# Fortin33.net
KiCad netlist of a schematic drawn in EAGLE
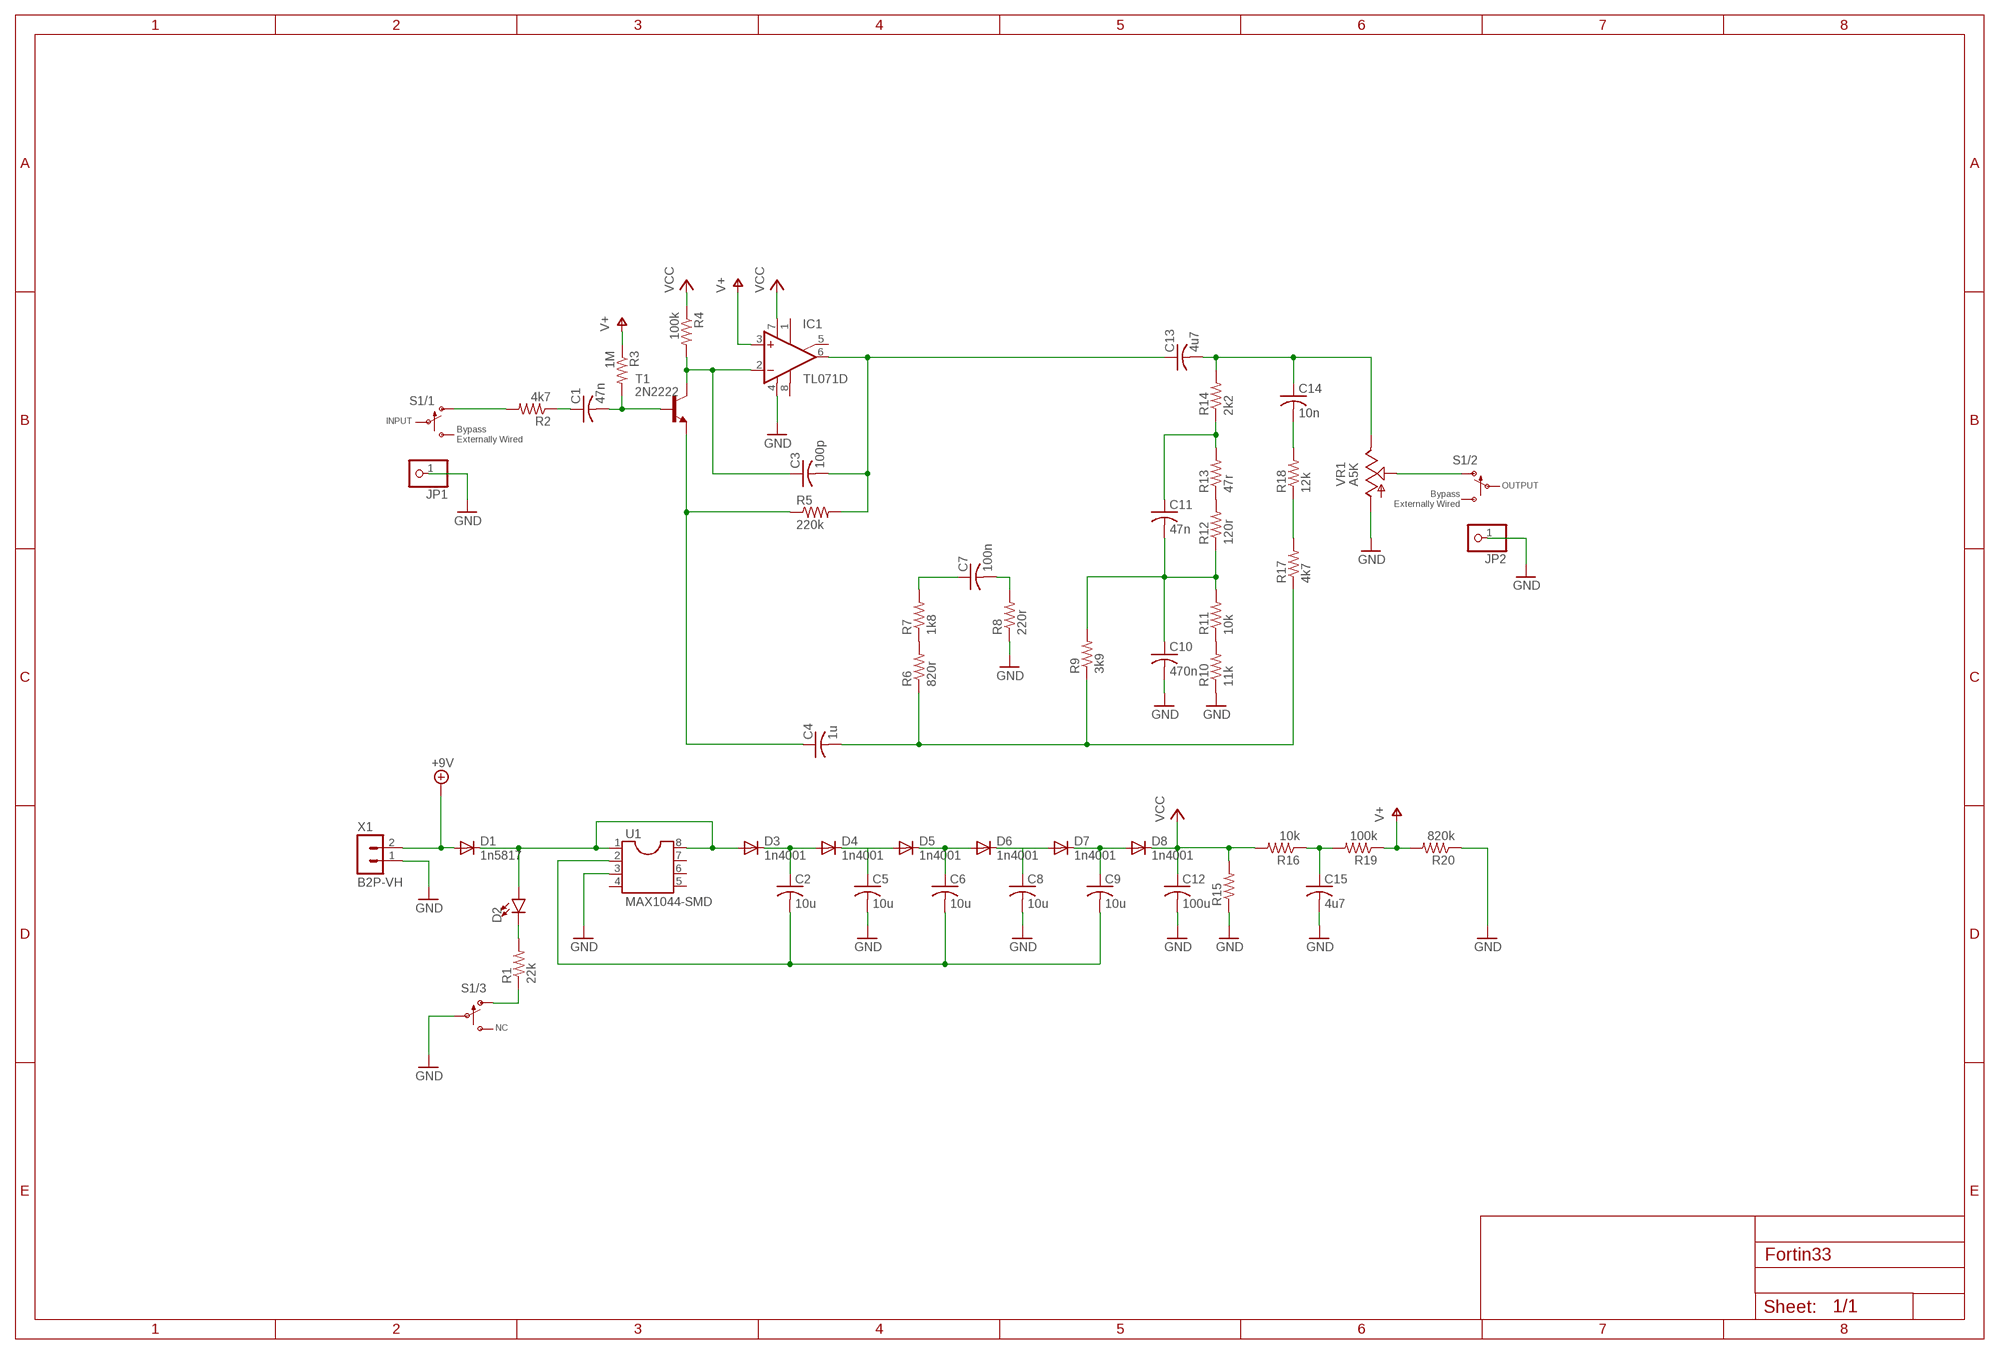
[diagram p0: schematic, sheet 1]

(export (version "E")
  (design (tool "Eeschema 10.0.6"))
  (components
    (comp (ref "C1")
      (value "47n")
      (footprint "eagle-import:C0603")
      (libsource (lib "eagle-import") (part "C-USC0603"))
    )
    (comp (ref "C2")
      (value "10u")
      (footprint "eagle-import:C050-025X075")
      (libsource (lib "eagle-import") (part "C-US050-025X075"))
    )
    (comp (ref "C3")
      (value "100p")
      (footprint "eagle-import:C0603")
      (libsource (lib "eagle-import") (part "C-USC0603"))
    )
    (comp (ref "C4")
      (value "1u")
      (footprint "eagle-import:C0603")
      (libsource (lib "eagle-import") (part "C-USC0603"))
    )
    (comp (ref "C5")
      (value "10u")
      (footprint "eagle-import:C050-025X075")
      (libsource (lib "eagle-import") (part "C-US050-025X075"))
    )
    (comp (ref "C6")
      (value "10u")
      (footprint "eagle-import:C050-025X075")
      (libsource (lib "eagle-import") (part "C-US050-025X075"))
    )
    (comp (ref "C7")
      (value "100n")
      (footprint "eagle-import:C0603")
      (libsource (lib "eagle-import") (part "C-USC0603"))
    )
    (comp (ref "C8")
      (value "10u")
      (footprint "eagle-import:C050-025X075")
      (libsource (lib "eagle-import") (part "C-US050-025X075"))
    )
    (comp (ref "C9")
      (value "10u")
      (footprint "eagle-import:C050-025X075")
      (libsource (lib "eagle-import") (part "C-US050-025X075"))
    )
    (comp (ref "C10")
      (value "470n")
      (footprint "eagle-import:C0603")
      (libsource (lib "eagle-import") (part "C-USC0603"))
    )
    (comp (ref "C11")
      (value "47n")
      (footprint "eagle-import:C0603")
      (libsource (lib "eagle-import") (part "C-USC0603"))
    )
    (comp (ref "C12")
      (value "100u")
      (footprint "eagle-import:C075-063X106")
      (libsource (lib "eagle-import") (part "C-US075-063X106"))
    )
    (comp (ref "C13")
      (value "4u7")
      (footprint "eagle-import:C0603")
      (libsource (lib "eagle-import") (part "C-USC0603"))
    )
    (comp (ref "C14")
      (value "10n")
      (footprint "eagle-import:C0603")
      (libsource (lib "eagle-import") (part "C-USC0603"))
    )
    (comp (ref "C15")
      (value "4u7")
      (footprint "eagle-import:C050-025X075")
      (libsource (lib "eagle-import") (part "C-US050-025X075"))
    )
    (comp (ref "D1")
      (value "1n5817")
      (footprint "eagle-import:DO41-10")
      (libsource (lib "eagle-import") (part "1N4004"))
    )
    (comp (ref "D2")
      (value "LED3MM")
      (footprint "eagle-import:LED_3MM")
      (libsource (lib "eagle-import") (part "LED3MM"))
    )
    (comp (ref "D3")
      (value "1n4001")
      (footprint "eagle-import:DO41-10")
      (libsource (lib "eagle-import") (part "1N4004"))
    )
    (comp (ref "D4")
      (value "1n4001")
      (footprint "eagle-import:DO41-10")
      (libsource (lib "eagle-import") (part "1N4004"))
    )
    (comp (ref "D5")
      (value "1n4001")
      (footprint "eagle-import:DO41-10")
      (libsource (lib "eagle-import") (part "1N4004"))
    )
    (comp (ref "D6")
      (value "1n4001")
      (footprint "eagle-import:DO41-10")
      (libsource (lib "eagle-import") (part "1N4004"))
    )
    (comp (ref "D7")
      (value "1n4001")
      (footprint "eagle-import:DO41-10")
      (libsource (lib "eagle-import") (part "1N4004"))
    )
    (comp (ref "D8")
      (value "1n4001")
      (footprint "eagle-import:DO41-10")
      (libsource (lib "eagle-import") (part "1N4004"))
    )
    (comp (ref "IC1")
      (value "TL071D")
      (footprint "eagle-import:SO08")
      (libsource (lib "eagle-import") (part "TL071D"))
    )
    (comp (ref "JP1")
      (value "PINHD-1X1")
      (footprint "eagle-import:1X01")
      (libsource (lib "eagle-import") (part "PINHD-1X1"))
    )
    (comp (ref "JP2")
      (value "PINHD-1X1")
      (footprint "eagle-import:1X01")
      (libsource (lib "eagle-import") (part "PINHD-1X1"))
    )
    (comp (ref "R1")
      (value "22k")
      (footprint "eagle-import:R0603")
      (libsource (lib "eagle-import") (part "R-US_R0603"))
    )
    (comp (ref "R2")
      (value "4k7")
      (footprint "eagle-import:R0603")
      (libsource (lib "eagle-import") (part "R-US_R0603"))
    )
    (comp (ref "R3")
      (value "1M")
      (footprint "eagle-import:R0603")
      (libsource (lib "eagle-import") (part "R-US_R0603"))
    )
    (comp (ref "R4")
      (value "100k")
      (footprint "eagle-import:R0603")
      (libsource (lib "eagle-import") (part "R-US_R0603"))
    )
    (comp (ref "R5")
      (value "220k")
      (footprint "eagle-import:R0603")
      (libsource (lib "eagle-import") (part "R-US_R0603"))
    )
    (comp (ref "R6")
      (value "820r")
      (footprint "eagle-import:R0603")
      (libsource (lib "eagle-import") (part "R-US_R0603"))
    )
    (comp (ref "R7")
      (value "1k8")
      (footprint "eagle-import:R0603")
      (libsource (lib "eagle-import") (part "R-US_R0603"))
    )
    (comp (ref "R8")
      (value "220r")
      (footprint "eagle-import:R0603")
      (libsource (lib "eagle-import") (part "R-US_R0603"))
    )
    (comp (ref "R9")
      (value "3k9")
      (footprint "eagle-import:R0603")
      (libsource (lib "eagle-import") (part "R-US_R0603"))
    )
    (comp (ref "R10")
      (value "11k")
      (footprint "eagle-import:R0603")
      (libsource (lib "eagle-import") (part "R-US_R0603"))
    )
    (comp (ref "R11")
      (value "10k")
      (footprint "eagle-import:R0603")
      (libsource (lib "eagle-import") (part "R-US_R0603"))
    )
    (comp (ref "R12")
      (value "120r")
      (footprint "eagle-import:R0603")
      (libsource (lib "eagle-import") (part "R-US_R0603"))
    )
    (comp (ref "R13")
      (value "47r")
      (footprint "eagle-import:R0603")
      (libsource (lib "eagle-import") (part "R-US_R0603"))
    )
    (comp (ref "R14")
      (value "2k2")
      (footprint "eagle-import:R0603")
      (libsource (lib "eagle-import") (part "R-US_R0603"))
    )
    (comp (ref "R15")
      (value "R-US_R0603")
      (footprint "eagle-import:R0603")
      (libsource (lib "eagle-import") (part "R-US_R0603"))
    )
    (comp (ref "R16")
      (value "10k")
      (footprint "eagle-import:R0603")
      (libsource (lib "eagle-import") (part "R-US_R0603"))
    )
    (comp (ref "R17")
      (value "4k7")
      (footprint "eagle-import:R0603")
      (libsource (lib "eagle-import") (part "R-US_R0603"))
    )
    (comp (ref "R18")
      (value "12k")
      (footprint "eagle-import:R0603")
      (libsource (lib "eagle-import") (part "R-US_R0603"))
    )
    (comp (ref "R19")
      (value "100k")
      (footprint "eagle-import:R0603")
      (libsource (lib "eagle-import") (part "R-US_R0603"))
    )
    (comp (ref "R20")
      (value "820k")
      (footprint "eagle-import:R0603")
      (libsource (lib "eagle-import") (part "R-US_R0603"))
    )
    (comp (ref "S1")
      (value "SWITCH-3DPT-INLINE-BREAKOUT-BYPASS")
      (footprint "eagle-import:1X04")
      (libsource (lib "eagle-import") (part "SWITCH-3DPT-INLINE-BREAKOUT-BYPASS"))
    )
    (comp (ref "T1")
      (value "2N2222")
      (footprint "eagle-import:TO92-EBC-OVAL")
      (libsource (lib "eagle-import") (part "2N2222"))
    )
    (comp (ref "U1")
      (value "MAX1044-SMD")
      (footprint "eagle-import:SO-08")
      (libsource (lib "eagle-import") (part "MAX1044-SMD"))
    )
    (comp (ref "VR1")
      (value "A5K")
      (footprint "eagle-import:ALPHA-16-MINI")
      (libsource (lib "eagle-import") (part "16MM-POT"))
    )
    (comp (ref "X1")
      (value "B2P-VH")
      (footprint "eagle-import:B2P-VH")
      (libsource (lib "eagle-import") (part "B2P-VH"))
    )
  )
  (nets
    (net (code "1") (name "+9V") (class "Default")
      (node (ref "D1") (pin "A") (pinfunction "A_A") (pintype "passive"))
      (node (ref "X1") (pin "2") (pinfunction "2_2") (pintype "passive"))
    )
    (net (code "2") (name "GND") (class "Default")
      (node (ref "C10") (pin "2") (pinfunction "2_2") (pintype "passive"))
      (node (ref "C12") (pin "2") (pinfunction "2_2") (pintype "passive"))
      (node (ref "C15") (pin "2") (pinfunction "2_2") (pintype "passive"))
      (node (ref "C5") (pin "2") (pinfunction "2_2") (pintype "passive"))
      (node (ref "C8") (pin "2") (pinfunction "2_2") (pintype "passive"))
      (node (ref "IC1") (pin "4") (pinfunction "V-_4") (pintype "power_in"))
      (node (ref "JP1") (pin "1") (pinfunction "1_1") (pintype "passive"))
      (node (ref "JP2") (pin "1") (pinfunction "1_1") (pintype "passive"))
      (node (ref "R10") (pin "1") (pinfunction "1_1") (pintype "passive"))
      (node (ref "R15") (pin "1") (pinfunction "1_1") (pintype "passive"))
      (node (ref "R20") (pin "1") (pinfunction "1_1") (pintype "passive"))
      (node (ref "R8") (pin "1") (pinfunction "1_1") (pintype "passive"))
      (node (ref "S1") (pin "3") (pinfunction "COMMON_3") (pintype "passive"))
      (node (ref "U1") (pin "3") (pinfunction "3_3") (pintype "passive"))
      (node (ref "VR1") (pin "LEFT") (pinfunction "LEFT_LEFT") (pintype "passive"))
      (node (ref "X1") (pin "1") (pinfunction "1_1") (pintype "passive"))
    )
    (net (code "3") (name "Net-(C1-Pad1)") (class "Default")
      (node (ref "C1") (pin "1") (pinfunction "1_1") (pintype "passive"))
      (node (ref "R2") (pin "1") (pinfunction "1_1") (pintype "passive"))
    )
    (net (code "4") (name "Net-(C1-Pad2)") (class "Default")
      (node (ref "C1") (pin "2") (pinfunction "2_2") (pintype "passive"))
      (node (ref "R3") (pin "2") (pinfunction "2_2") (pintype "passive"))
      (node (ref "T1") (pin "B") (pinfunction "B_B") (pintype "passive"))
    )
    (net (code "5") (name "Net-(C2-Pad1)") (class "Default")
      (node (ref "C2") (pin "1") (pinfunction "1_1") (pintype "passive"))
      (node (ref "D3") (pin "C") (pinfunction "C_C") (pintype "passive"))
      (node (ref "D4") (pin "A") (pinfunction "A_A") (pintype "passive"))
    )
    (net (code "6") (name "Net-(C2-Pad2)") (class "Default")
      (node (ref "C2") (pin "2") (pinfunction "2_2") (pintype "passive"))
      (node (ref "C6") (pin "2") (pinfunction "2_2") (pintype "passive"))
      (node (ref "C9") (pin "2") (pinfunction "2_2") (pintype "passive"))
      (node (ref "U1") (pin "2") (pinfunction "2_2") (pintype "passive"))
    )
    (net (code "7") (name "Net-(C4-Pad1)") (class "Default")
      (node (ref "C4") (pin "1") (pinfunction "1_1") (pintype "passive"))
      (node (ref "R5") (pin "1") (pinfunction "1_1") (pintype "passive"))
      (node (ref "T1") (pin "E") (pinfunction "E_E") (pintype "passive"))
    )
    (net (code "8") (name "Net-(C4-Pad2)") (class "Default")
      (node (ref "C4") (pin "2") (pinfunction "2_2") (pintype "passive"))
      (node (ref "R17") (pin "1") (pinfunction "1_1") (pintype "passive"))
      (node (ref "R6") (pin "1") (pinfunction "1_1") (pintype "passive"))
      (node (ref "R9") (pin "1") (pinfunction "1_1") (pintype "passive"))
    )
    (net (code "9") (name "Net-(C5-Pad1)") (class "Default")
      (node (ref "C5") (pin "1") (pinfunction "1_1") (pintype "passive"))
      (node (ref "D4") (pin "C") (pinfunction "C_C") (pintype "passive"))
      (node (ref "D5") (pin "A") (pinfunction "A_A") (pintype "passive"))
    )
    (net (code "10") (name "Net-(C6-Pad1)") (class "Default")
      (node (ref "C6") (pin "1") (pinfunction "1_1") (pintype "passive"))
      (node (ref "D5") (pin "C") (pinfunction "C_C") (pintype "passive"))
      (node (ref "D6") (pin "A") (pinfunction "A_A") (pintype "passive"))
    )
    (net (code "11") (name "Net-(C7-Pad1)") (class "Default")
      (node (ref "C7") (pin "1") (pinfunction "1_1") (pintype "passive"))
      (node (ref "R7") (pin "2") (pinfunction "2_2") (pintype "passive"))
    )
    (net (code "12") (name "Net-(C7-Pad2)") (class "Default")
      (node (ref "C7") (pin "2") (pinfunction "2_2") (pintype "passive"))
      (node (ref "R8") (pin "2") (pinfunction "2_2") (pintype "passive"))
    )
    (net (code "13") (name "Net-(C8-Pad1)") (class "Default")
      (node (ref "C8") (pin "1") (pinfunction "1_1") (pintype "passive"))
      (node (ref "D6") (pin "C") (pinfunction "C_C") (pintype "passive"))
      (node (ref "D7") (pin "A") (pinfunction "A_A") (pintype "passive"))
    )
    (net (code "14") (name "Net-(C9-Pad1)") (class "Default")
      (node (ref "C9") (pin "1") (pinfunction "1_1") (pintype "passive"))
      (node (ref "D7") (pin "C") (pinfunction "C_C") (pintype "passive"))
      (node (ref "D8") (pin "A") (pinfunction "A_A") (pintype "passive"))
    )
    (net (code "15") (name "Net-(C10-Pad1)") (class "Default")
      (node (ref "C10") (pin "1") (pinfunction "1_1") (pintype "passive"))
      (node (ref "C11") (pin "2") (pinfunction "2_2") (pintype "passive"))
      (node (ref "R11") (pin "2") (pinfunction "2_2") (pintype "passive"))
      (node (ref "R12") (pin "1") (pinfunction "1_1") (pintype "passive"))
      (node (ref "R9") (pin "2") (pinfunction "2_2") (pintype "passive"))
    )
    (net (code "16") (name "Net-(C11-Pad1)") (class "Default")
      (node (ref "C11") (pin "1") (pinfunction "1_1") (pintype "passive"))
      (node (ref "R13") (pin "2") (pinfunction "2_2") (pintype "passive"))
      (node (ref "R14") (pin "1") (pinfunction "1_1") (pintype "passive"))
    )
    (net (code "17") (name "Net-(C13-Pad2)") (class "Default")
      (node (ref "C13") (pin "2") (pinfunction "2_2") (pintype "passive"))
      (node (ref "C14") (pin "1") (pinfunction "1_1") (pintype "passive"))
      (node (ref "R14") (pin "2") (pinfunction "2_2") (pintype "passive"))
      (node (ref "VR1") (pin "RIGHT") (pinfunction "RIGHT_RIGHT") (pintype "passive"))
    )
    (net (code "18") (name "Net-(C14-Pad2)") (class "Default")
      (node (ref "C14") (pin "2") (pinfunction "2_2") (pintype "passive"))
      (node (ref "R18") (pin "2") (pinfunction "2_2") (pintype "passive"))
    )
    (net (code "19") (name "Net-(C15-Pad1)") (class "Default")
      (node (ref "C15") (pin "1") (pinfunction "1_1") (pintype "passive"))
      (node (ref "R16") (pin "1") (pinfunction "1_1") (pintype "passive"))
      (node (ref "R19") (pin "2") (pinfunction "2_2") (pintype "passive"))
    )
    (net (code "20") (name "Net-(D1-PadC)") (class "Default")
      (node (ref "D1") (pin "C") (pinfunction "C_C") (pintype "passive"))
      (node (ref "D2") (pin "A") (pinfunction "A_A") (pintype "passive"))
      (node (ref "D3") (pin "A") (pinfunction "A_A") (pintype "passive"))
      (node (ref "U1") (pin "1") (pinfunction "1_1") (pintype "passive"))
      (node (ref "U1") (pin "8") (pinfunction "8_8") (pintype "passive"))
    )
    (net (code "21") (name "Net-(D2-C)") (class "Default")
      (node (ref "D2") (pin "K") (pinfunction "C_K") (pintype "passive"))
      (node (ref "R1") (pin "2") (pinfunction "2_2") (pintype "passive"))
    )
    (net (code "22") (name "Net-(IC1--IN)") (class "Default")
      (node (ref "C3") (pin "1") (pinfunction "1_1") (pintype "passive"))
      (node (ref "IC1") (pin "2") (pinfunction "-IN_2") (pintype "input"))
      (node (ref "R4") (pin "2") (pinfunction "2_2") (pintype "passive"))
      (node (ref "T1") (pin "C") (pinfunction "C_C") (pintype "passive"))
    )
    (net (code "23") (name "Net-(IC1-OUT)") (class "Default")
      (node (ref "C13") (pin "1") (pinfunction "1_1") (pintype "passive"))
      (node (ref "C3") (pin "2") (pinfunction "2_2") (pintype "passive"))
      (node (ref "IC1") (pin "6") (pinfunction "OUT_6") (pintype "output"))
      (node (ref "R5") (pin "2") (pinfunction "2_2") (pintype "passive"))
    )
    (net (code "24") (name "Net-(R6-Pad2)") (class "Default")
      (node (ref "R6") (pin "2") (pinfunction "2_2") (pintype "passive"))
      (node (ref "R7") (pin "1") (pinfunction "1_1") (pintype "passive"))
    )
    (net (code "25") (name "Net-(R10-Pad2)") (class "Default")
      (node (ref "R10") (pin "2") (pinfunction "2_2") (pintype "passive"))
      (node (ref "R11") (pin "1") (pinfunction "1_1") (pintype "passive"))
    )
    (net (code "26") (name "Net-(R12-Pad2)") (class "Default")
      (node (ref "R12") (pin "2") (pinfunction "2_2") (pintype "passive"))
      (node (ref "R13") (pin "1") (pinfunction "1_1") (pintype "passive"))
    )
    (net (code "27") (name "Net-(R17-Pad2)") (class "Default")
      (node (ref "R17") (pin "2") (pinfunction "2_2") (pintype "passive"))
      (node (ref "R18") (pin "1") (pinfunction "1_1") (pintype "passive"))
    )
    (net (code "28") (name "Net-(S1A-NORMALLY-ON)") (class "Default")
      (node (ref "R2") (pin "2") (pinfunction "2_2") (pintype "passive"))
      (node (ref "S1") (pin "1") (pinfunction "NORMALLY-ON_1") (pintype "passive"))
    )
    (net (code "29") (name "Net-(S1B-NORMALLY-ON)") (class "Default")
      (node (ref "S1") (pin "2") (pinfunction "NORMALLY-ON_2") (pintype "passive"))
      (node (ref "VR1") (pin "WIPER") (pinfunction "WIPER_WIPER") (pintype "passive"))
    )
    (net (code "30") (name "Net-(S1C-NORMALLY-ON)") (class "Default")
      (node (ref "R1") (pin "1") (pinfunction "1_1") (pintype "passive"))
      (node (ref "S1") (pin "4") (pinfunction "NORMALLY-ON_4") (pintype "passive"))
    )
    (net (code "31") (name "V+") (class "Default")
      (node (ref "IC1") (pin "3") (pinfunction "+IN_3") (pintype "input"))
      (node (ref "R19") (pin "1") (pinfunction "1_1") (pintype "passive"))
      (node (ref "R20") (pin "2") (pinfunction "2_2") (pintype "passive"))
      (node (ref "R3") (pin "1") (pinfunction "1_1") (pintype "passive"))
    )
    (net (code "32") (name "VCC") (class "Default")
      (node (ref "C12") (pin "1") (pinfunction "1_1") (pintype "passive"))
      (node (ref "D8") (pin "C") (pinfunction "C_C") (pintype "passive"))
      (node (ref "IC1") (pin "7") (pinfunction "V+_7") (pintype "power_in"))
      (node (ref "R15") (pin "2") (pinfunction "2_2") (pintype "passive"))
      (node (ref "R16") (pin "2") (pinfunction "2_2") (pintype "passive"))
      (node (ref "R4") (pin "1") (pinfunction "1_1") (pintype "passive"))
    )
    (net (code "33") (name "unconnected-(IC1-ON1-Pad1)") (class "Default")
      (node (ref "IC1") (pin "1") (pinfunction "ON1_1") (pintype "passive"))
    )
    (net (code "34") (name "unconnected-(IC1-ON2-Pad5)") (class "Default")
      (node (ref "IC1") (pin "5") (pinfunction "ON2_5") (pintype "passive"))
    )
    (net (code "35") (name "unconnected-(IC1-OPT-Pad8)") (class "Default")
      (node (ref "IC1") (pin "8") (pinfunction "OPT_8") (pintype "passive"))
    )
    (net (code "36") (name "unconnected-(U1-Pad4)") (class "Default")
      (node (ref "U1") (pin "4") (pinfunction "4_4") (pintype "passive"))
    )
    (net (code "37") (name "unconnected-(U1-Pad5)") (class "Default")
      (node (ref "U1") (pin "5") (pinfunction "5_5") (pintype "passive"))
    )
    (net (code "38") (name "unconnected-(U1-Pad6)") (class "Default")
      (node (ref "U1") (pin "6") (pinfunction "6_6") (pintype "passive"))
    )
    (net (code "39") (name "unconnected-(U1-Pad7)") (class "Default")
      (node (ref "U1") (pin "7") (pinfunction "7_7") (pintype "passive"))
    )
  )
)
